# pcb-inductive-sensor2.net
KiCad netlist of a schematic drawn in EAGLE
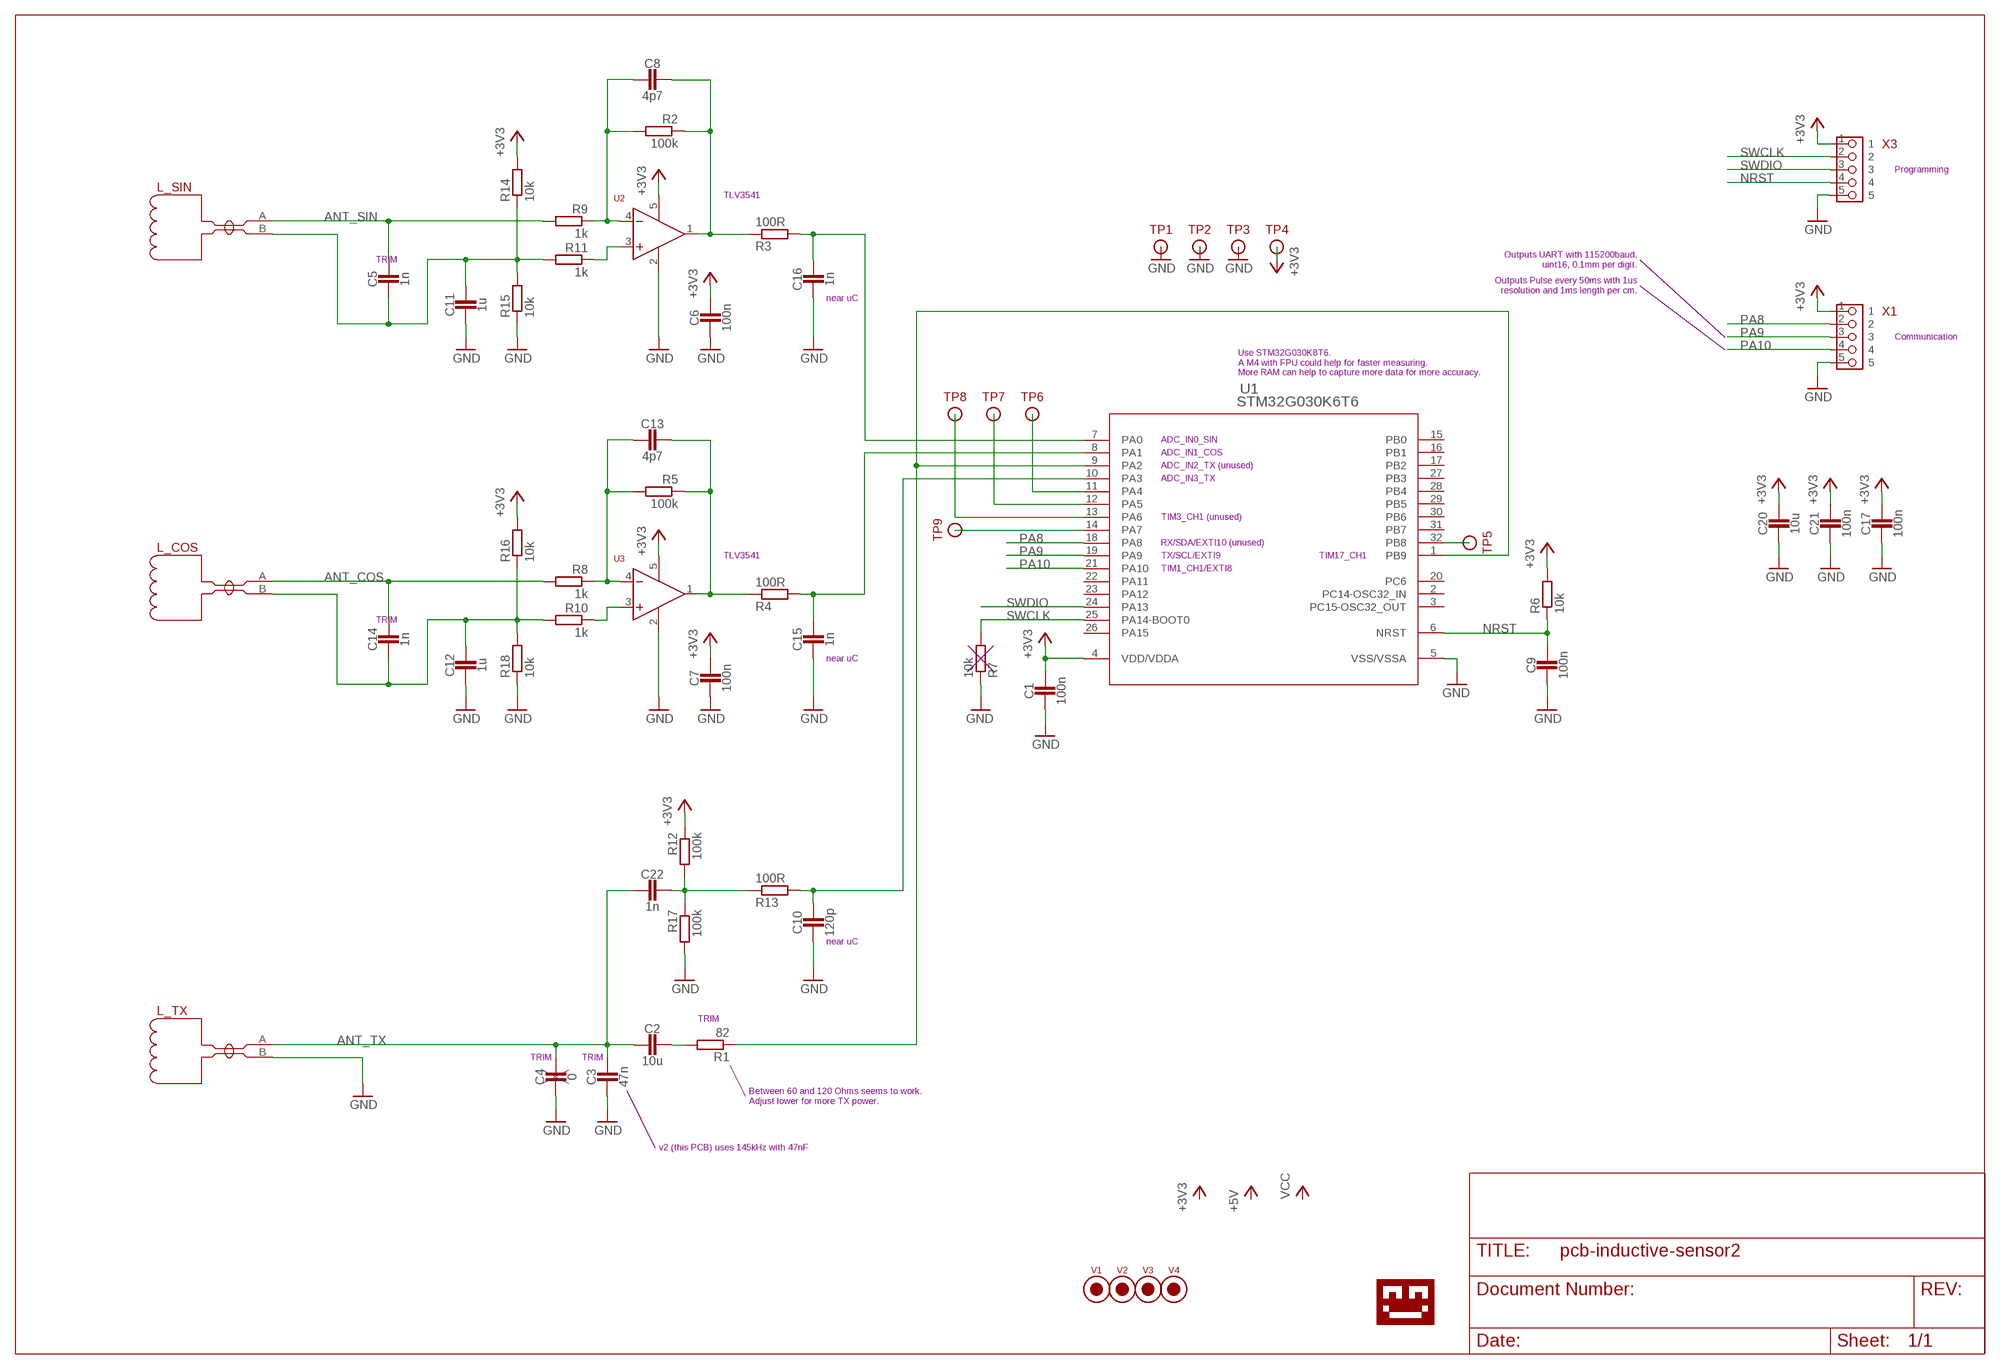
[diagram p0: schematic, sheet 1]

(export (version "E")
  (design (tool "Eeschema 10.0.6"))
  (components
    (comp (ref "C1")
      (value "100n")
      (footprint "eagle-import:0603_CAP")
      (libsource (lib "eagle-import") (part "CAPACITOR0603_CAP"))
    )
    (comp (ref "C2")
      (value "10u")
      (footprint "eagle-import:0805_CAP")
      (libsource (lib "eagle-import") (part "CAPACITOR0805_CAP"))
    )
    (comp (ref "C3")
      (value "47n")
      (footprint "eagle-import:0603_CAP")
      (libsource (lib "eagle-import") (part "CAPACITOR0603_CAP"))
    )
    (comp (ref "C4")
      (value "0")
      (footprint "eagle-import:0603_CAP")
      (libsource (lib "eagle-import") (part "CAPACITOR0603_CAP"))
    )
    (comp (ref "C5")
      (value "1n")
      (footprint "eagle-import:0603_CAP")
      (libsource (lib "eagle-import") (part "CAPACITOR0603_CAP"))
    )
    (comp (ref "C6")
      (value "100n")
      (footprint "eagle-import:0603_CAP")
      (libsource (lib "eagle-import") (part "CAPACITOR0603_CAP"))
    )
    (comp (ref "C7")
      (value "100n")
      (footprint "eagle-import:0603_CAP")
      (libsource (lib "eagle-import") (part "CAPACITOR0603_CAP"))
    )
    (comp (ref "C8")
      (value "4p7")
      (footprint "eagle-import:0603_CAP")
      (libsource (lib "eagle-import") (part "CAPACITOR0603_CAP"))
    )
    (comp (ref "C9")
      (value "100n")
      (footprint "eagle-import:0603_CAP")
      (libsource (lib "eagle-import") (part "CAPACITOR0603_CAP"))
    )
    (comp (ref "C10")
      (value "120p")
      (footprint "eagle-import:0603_CAP")
      (libsource (lib "eagle-import") (part "CAPACITOR0603_CAP"))
    )
    (comp (ref "C11")
      (value "1u")
      (footprint "eagle-import:0603_CAP")
      (libsource (lib "eagle-import") (part "CAPACITOR0603_CAP"))
    )
    (comp (ref "C12")
      (value "1u")
      (footprint "eagle-import:0603_CAP")
      (libsource (lib "eagle-import") (part "CAPACITOR0603_CAP"))
    )
    (comp (ref "C13")
      (value "4p7")
      (footprint "eagle-import:0603_CAP")
      (libsource (lib "eagle-import") (part "CAPACITOR0603_CAP"))
    )
    (comp (ref "C14")
      (value "1n")
      (footprint "eagle-import:0603_CAP")
      (libsource (lib "eagle-import") (part "CAPACITOR0603_CAP"))
    )
    (comp (ref "C15")
      (value "1n")
      (footprint "eagle-import:0603_CAP")
      (libsource (lib "eagle-import") (part "CAPACITOR0603_CAP"))
    )
    (comp (ref "C16")
      (value "1n")
      (footprint "eagle-import:0603_CAP")
      (libsource (lib "eagle-import") (part "CAPACITOR0603_CAP"))
    )
    (comp (ref "C17")
      (value "100n")
      (footprint "eagle-import:0603_CAP")
      (libsource (lib "eagle-import") (part "CAPACITOR0603_CAP"))
    )
    (comp (ref "C20")
      (value "10u")
      (footprint "eagle-import:0805_CAP")
      (libsource (lib "eagle-import") (part "CAPACITOR0805_CAP"))
    )
    (comp (ref "C21")
      (value "100n")
      (footprint "eagle-import:0603_CAP")
      (libsource (lib "eagle-import") (part "CAPACITOR0603_CAP"))
    )
    (comp (ref "C22")
      (value "1n")
      (footprint "eagle-import:0603_CAP")
      (libsource (lib "eagle-import") (part "CAPACITOR0603_CAP"))
    )
    (comp (ref "L_COS")
      (value "INDUCTION_SENSOR")
      (footprint "eagle-import:INDUCTIVE_SENSOR_NET_TIE")
      (libsource (lib "eagle-import") (part "INDUCTION_SENSOR"))
    )
    (comp (ref "L_SIN")
      (value "INDUCTION_SENSOR")
      (footprint "eagle-import:INDUCTIVE_SENSOR_NET_TIE")
      (libsource (lib "eagle-import") (part "INDUCTION_SENSOR"))
    )
    (comp (ref "L_TX")
      (value "INDUCTION_SENSOR")
      (footprint "eagle-import:INDUCTIVE_SENSOR_NET_TIE")
      (libsource (lib "eagle-import") (part "INDUCTION_SENSOR"))
    )
    (comp (ref "R1")
      (value "82")
      (footprint "eagle-import:0805_RES")
      (libsource (lib "eagle-import") (part "RESISTOR0805_RES"))
    )
    (comp (ref "R2")
      (value "100k")
      (footprint "eagle-import:0603-RES")
      (libsource (lib "eagle-import") (part "RESISTOR0603_RES"))
    )
    (comp (ref "R3")
      (value "100R")
      (footprint "eagle-import:0603-RES")
      (libsource (lib "eagle-import") (part "RESISTOR0603_RES"))
    )
    (comp (ref "R4")
      (value "100R")
      (footprint "eagle-import:0603-RES")
      (libsource (lib "eagle-import") (part "RESISTOR0603_RES"))
    )
    (comp (ref "R5")
      (value "100k")
      (footprint "eagle-import:0603-RES")
      (libsource (lib "eagle-import") (part "RESISTOR0603_RES"))
    )
    (comp (ref "R6")
      (value "10k")
      (footprint "eagle-import:0603-RES")
      (libsource (lib "eagle-import") (part "RESISTOR0603_RES"))
    )
    (comp (ref "R7")
      (value "10k")
      (footprint "eagle-import:0603-RES")
      (libsource (lib "eagle-import") (part "RESISTOR0603_RES"))
    )
    (comp (ref "R8")
      (value "1k")
      (footprint "eagle-import:0603-RES")
      (libsource (lib "eagle-import") (part "RESISTOR0603_RES"))
    )
    (comp (ref "R9")
      (value "1k")
      (footprint "eagle-import:0603-RES")
      (libsource (lib "eagle-import") (part "RESISTOR0603_RES"))
    )
    (comp (ref "R10")
      (value "1k")
      (footprint "eagle-import:0603-RES")
      (libsource (lib "eagle-import") (part "RESISTOR0603_RES"))
    )
    (comp (ref "R11")
      (value "1k")
      (footprint "eagle-import:0603-RES")
      (libsource (lib "eagle-import") (part "RESISTOR0603_RES"))
    )
    (comp (ref "R12")
      (value "100k")
      (footprint "eagle-import:0603-RES")
      (libsource (lib "eagle-import") (part "RESISTOR0603_RES"))
    )
    (comp (ref "R13")
      (value "100R")
      (footprint "eagle-import:0603-RES")
      (libsource (lib "eagle-import") (part "RESISTOR0603_RES"))
    )
    (comp (ref "R14")
      (value "10k")
      (footprint "eagle-import:0603-RES")
      (libsource (lib "eagle-import") (part "RESISTOR0603_RES"))
    )
    (comp (ref "R15")
      (value "10k")
      (footprint "eagle-import:0603-RES")
      (libsource (lib "eagle-import") (part "RESISTOR0603_RES"))
    )
    (comp (ref "R16")
      (value "10k")
      (footprint "eagle-import:0603-RES")
      (libsource (lib "eagle-import") (part "RESISTOR0603_RES"))
    )
    (comp (ref "R17")
      (value "100k")
      (footprint "eagle-import:0603-RES")
      (libsource (lib "eagle-import") (part "RESISTOR0603_RES"))
    )
    (comp (ref "R18")
      (value "10k")
      (footprint "eagle-import:0603-RES")
      (libsource (lib "eagle-import") (part "RESISTOR0603_RES"))
    )
    (comp (ref "TP1")
      (value "TESTPIN")
      (footprint "eagle-import:PIN-SMD-1X1-TEST_1M5")
      (libsource (lib "eagle-import") (part "TESTPIN"))
    )
    (comp (ref "TP2")
      (value "TESTPIN")
      (footprint "eagle-import:PIN-SMD-1X1-TEST_1M5")
      (libsource (lib "eagle-import") (part "TESTPIN"))
    )
    (comp (ref "TP3")
      (value "TESTPIN")
      (footprint "eagle-import:PIN-SMD-1X1-TEST_1M5")
      (libsource (lib "eagle-import") (part "TESTPIN"))
    )
    (comp (ref "TP4")
      (value "TESTPIN")
      (footprint "eagle-import:PIN-SMD-1X1-TEST_1M5")
      (libsource (lib "eagle-import") (part "TESTPIN"))
    )
    (comp (ref "TP5")
      (value "TESTPIN")
      (footprint "eagle-import:PIN-SMD-1X1-TEST_1M5")
      (libsource (lib "eagle-import") (part "TESTPIN"))
    )
    (comp (ref "TP6")
      (value "TESTPIN")
      (footprint "eagle-import:PIN-SMD-1X1-TEST_1M5")
      (libsource (lib "eagle-import") (part "TESTPIN"))
    )
    (comp (ref "TP7")
      (value "TESTPIN")
      (footprint "eagle-import:PIN-SMD-1X1-TEST_1M5")
      (libsource (lib "eagle-import") (part "TESTPIN"))
    )
    (comp (ref "TP8")
      (value "TESTPIN")
      (footprint "eagle-import:PIN-SMD-1X1-TEST_1M5")
      (libsource (lib "eagle-import") (part "TESTPIN"))
    )
    (comp (ref "TP9")
      (value "TESTPIN")
      (footprint "eagle-import:PIN-SMD-1X1-TEST_1M5")
      (libsource (lib "eagle-import") (part "TESTPIN"))
    )
    (comp (ref "U$1")
      (value "LOGO-TOBENG-1MM-FINISH")
      (footprint "eagle-import:TOBENG-1MM-FINISH")
      (libsource (lib "eagle-import") (part "LOGO-TOBENG-1MM-FINISH"))
    )
    (comp (ref "U1")
      (value "STM32G030K6T6")
      (footprint "eagle-import:LQFP-32")
      (fields (field (name "COPYRIGHT") "Copyright (C) 2018 Accelerated Designs. All rights reserved"))
      (libsource (lib "eagle-import") (part "STM32G030K6T6"))
    )
    (comp (ref "U2")
      (value "OPAMP-TLV3541IDBVT")
      (footprint "eagle-import:SOT-23-5")
      (libsource (lib "eagle-import") (part "OPAMP-TLV3541IDBVT"))
    )
    (comp (ref "U3")
      (value "OPAMP-TLV3541IDBVT")
      (footprint "eagle-import:SOT-23-5")
      (libsource (lib "eagle-import") (part "OPAMP-TLV3541IDBVT"))
    )
    (comp (ref "V1")
      (value "FIDUCIAL2MM")
      (footprint "eagle-import:FIDUCIAL_2MM")
      (libsource (lib "eagle-import") (part "FIDUCIAL2MM"))
    )
    (comp (ref "V2")
      (value "FIDUCIAL2MM")
      (footprint "eagle-import:FIDUCIAL_2MM")
      (libsource (lib "eagle-import") (part "FIDUCIAL2MM"))
    )
    (comp (ref "V3")
      (value "FIDUCIAL2MM")
      (footprint "eagle-import:FIDUCIAL_2MM")
      (libsource (lib "eagle-import") (part "FIDUCIAL2MM"))
    )
    (comp (ref "V4")
      (value "FIDUCIAL2MM")
      (footprint "eagle-import:FIDUCIAL_2MM")
      (libsource (lib "eagle-import") (part "FIDUCIAL2MM"))
    )
    (comp (ref "X1")
      (value "PIN_5X1HD")
      (footprint "eagle-import:PIN_5X1_HD")
      (libsource (lib "eagle-import") (part "PIN_5X1HD"))
    )
    (comp (ref "X3")
      (value "PIN_5X1HD")
      (footprint "eagle-import:PIN_5X1_HD")
      (libsource (lib "eagle-import") (part "PIN_5X1HD"))
    )
  )
  (nets
    (net (code "1") (name "+3V3") (class "Default")
      (node (ref "C1") (pin "1") (pinfunction "1_1") (pintype "bidirectional"))
      (node (ref "C17") (pin "1") (pinfunction "1_1") (pintype "bidirectional"))
      (node (ref "C20") (pin "P$1") (pinfunction "1_P$1") (pintype "bidirectional"))
      (node (ref "C21") (pin "1") (pinfunction "1_1") (pintype "bidirectional"))
      (node (ref "C6") (pin "1") (pinfunction "1_1") (pintype "bidirectional"))
      (node (ref "C7") (pin "1") (pinfunction "1_1") (pintype "bidirectional"))
      (node (ref "R12") (pin "1") (pinfunction "1_1") (pintype "passive"))
      (node (ref "R14") (pin "2") (pinfunction "2_2") (pintype "passive"))
      (node (ref "R16") (pin "2") (pinfunction "2_2") (pintype "passive"))
      (node (ref "R6") (pin "2") (pinfunction "2_2") (pintype "passive"))
      (node (ref "TP4") (pin "1") (pinfunction "1_1") (pintype "bidirectional"))
      (node (ref "U1") (pin "4") (pinfunction "VDD/VDDA_4") (pintype "power_in"))
      (node (ref "U2") (pin "5") (pinfunction "VCC_5") (pintype "bidirectional"))
      (node (ref "U3") (pin "5") (pinfunction "VCC_5") (pintype "bidirectional"))
      (node (ref "X1") (pin "1") (pinfunction "1_1") (pintype "bidirectional"))
      (node (ref "X3") (pin "1") (pinfunction "1_1") (pintype "bidirectional"))
    )
    (net (code "3") (name "/ANT_COS") (class "Default")
      (node (ref "C14") (pin "1") (pinfunction "1_1") (pintype "bidirectional"))
      (node (ref "L_COS") (pin "A") (pinfunction "A_A") (pintype "bidirectional"))
      (node (ref "R8") (pin "2") (pinfunction "2_2") (pintype "passive"))
    )
    (net (code "4") (name "/ANT_SIN") (class "Default")
      (node (ref "C5") (pin "1") (pinfunction "1_1") (pintype "bidirectional"))
      (node (ref "L_SIN") (pin "A") (pinfunction "A_A") (pintype "bidirectional"))
      (node (ref "R9") (pin "2") (pinfunction "2_2") (pintype "passive"))
    )
    (net (code "5") (name "/ANT_TX") (class "Default")
      (node (ref "C2") (pin "P$2") (pinfunction "2_P$2") (pintype "bidirectional"))
      (node (ref "C22") (pin "2") (pinfunction "2_2") (pintype "bidirectional"))
      (node (ref "C3") (pin "1") (pinfunction "1_1") (pintype "bidirectional"))
      (node (ref "C4") (pin "1") (pinfunction "1_1") (pintype "bidirectional"))
      (node (ref "L_TX") (pin "A") (pinfunction "A_A") (pintype "bidirectional"))
    )
    (net (code "6") (name "/NRST") (class "Default")
      (node (ref "C9") (pin "1") (pinfunction "1_1") (pintype "bidirectional"))
      (node (ref "R6") (pin "1") (pinfunction "1_1") (pintype "passive"))
      (node (ref "U1") (pin "6") (pinfunction "NRST_6") (pintype "bidirectional"))
      (node (ref "X3") (pin "4") (pinfunction "4_4") (pintype "bidirectional"))
    )
    (net (code "7") (name "/PA8") (class "Default")
      (node (ref "U1") (pin "18") (pinfunction "PA8_18") (pintype "bidirectional"))
      (node (ref "X1") (pin "2") (pinfunction "2_2") (pintype "bidirectional"))
    )
    (net (code "8") (name "/PA9") (class "Default")
      (node (ref "U1") (pin "19") (pinfunction "PA9_19") (pintype "bidirectional"))
      (node (ref "X1") (pin "3") (pinfunction "3_3") (pintype "bidirectional"))
    )
    (net (code "9") (name "/PA10") (class "Default")
      (node (ref "U1") (pin "21") (pinfunction "PA10_21") (pintype "bidirectional"))
      (node (ref "X1") (pin "4") (pinfunction "4_4") (pintype "bidirectional"))
    )
    (net (code "10") (name "/SWCLK") (class "Default")
      (node (ref "R7") (pin "2") (pinfunction "2_2") (pintype "passive"))
      (node (ref "U1") (pin "25") (pinfunction "PA14-BOOT0_25") (pintype "bidirectional"))
      (node (ref "X3") (pin "2") (pinfunction "2_2") (pintype "bidirectional"))
    )
    (net (code "11") (name "/SWDIO") (class "Default")
      (node (ref "U1") (pin "24") (pinfunction "PA13_24") (pintype "bidirectional"))
      (node (ref "X3") (pin "3") (pinfunction "3_3") (pintype "bidirectional"))
    )
    (net (code "12") (name "GND") (class "Default")
      (node (ref "C1") (pin "2") (pinfunction "2_2") (pintype "bidirectional"))
      (node (ref "C10") (pin "2") (pinfunction "2_2") (pintype "bidirectional"))
      (node (ref "C11") (pin "2") (pinfunction "2_2") (pintype "bidirectional"))
      (node (ref "C12") (pin "2") (pinfunction "2_2") (pintype "bidirectional"))
      (node (ref "C15") (pin "2") (pinfunction "2_2") (pintype "bidirectional"))
      (node (ref "C16") (pin "2") (pinfunction "2_2") (pintype "bidirectional"))
      (node (ref "C17") (pin "2") (pinfunction "2_2") (pintype "bidirectional"))
      (node (ref "C20") (pin "P$2") (pinfunction "2_P$2") (pintype "bidirectional"))
      (node (ref "C21") (pin "2") (pinfunction "2_2") (pintype "bidirectional"))
      (node (ref "C3") (pin "2") (pinfunction "2_2") (pintype "bidirectional"))
      (node (ref "C4") (pin "2") (pinfunction "2_2") (pintype "bidirectional"))
      (node (ref "C6") (pin "2") (pinfunction "2_2") (pintype "bidirectional"))
      (node (ref "C7") (pin "2") (pinfunction "2_2") (pintype "bidirectional"))
      (node (ref "C9") (pin "2") (pinfunction "2_2") (pintype "bidirectional"))
      (node (ref "L_TX") (pin "B") (pinfunction "B_B") (pintype "bidirectional"))
      (node (ref "R15") (pin "1") (pinfunction "1_1") (pintype "passive"))
      (node (ref "R17") (pin "2") (pinfunction "2_2") (pintype "passive"))
      (node (ref "R18") (pin "1") (pinfunction "1_1") (pintype "passive"))
      (node (ref "R7") (pin "1") (pinfunction "1_1") (pintype "passive"))
      (node (ref "TP1") (pin "1") (pinfunction "1_1") (pintype "bidirectional"))
      (node (ref "TP2") (pin "1") (pinfunction "1_1") (pintype "bidirectional"))
      (node (ref "TP3") (pin "1") (pinfunction "1_1") (pintype "bidirectional"))
      (node (ref "U1") (pin "5") (pinfunction "VSS/VSSA_5") (pintype "power_in"))
      (node (ref "U2") (pin "2") (pinfunction "GND_2") (pintype "bidirectional"))
      (node (ref "U3") (pin "2") (pinfunction "GND_2") (pintype "bidirectional"))
      (node (ref "X1") (pin "5") (pinfunction "5_5") (pintype "bidirectional"))
      (node (ref "X3") (pin "5") (pinfunction "5_5") (pintype "bidirectional"))
    )
    (net (code "13") (name "Net-(C2-1)") (class "Default")
      (node (ref "C2") (pin "P$1") (pinfunction "1_P$1") (pintype "bidirectional"))
      (node (ref "R1") (pin "2") (pinfunction "2_2") (pintype "passive"))
    )
    (net (code "14") (name "Net-(C11-Pad1)") (class "Default")
      (node (ref "C11") (pin "1") (pinfunction "1_1") (pintype "bidirectional"))
      (node (ref "C5") (pin "2") (pinfunction "2_2") (pintype "bidirectional"))
      (node (ref "L_SIN") (pin "B") (pinfunction "B_B") (pintype "bidirectional"))
      (node (ref "R11") (pin "2") (pinfunction "2_2") (pintype "passive"))
      (node (ref "R14") (pin "1") (pinfunction "1_1") (pintype "passive"))
      (node (ref "R15") (pin "2") (pinfunction "2_2") (pintype "passive"))
    )
    (net (code "15") (name "Net-(C12-Pad1)") (class "Default")
      (node (ref "C12") (pin "1") (pinfunction "1_1") (pintype "bidirectional"))
      (node (ref "C14") (pin "2") (pinfunction "2_2") (pintype "bidirectional"))
      (node (ref "L_COS") (pin "B") (pinfunction "B_B") (pintype "bidirectional"))
      (node (ref "R10") (pin "2") (pinfunction "2_2") (pintype "passive"))
      (node (ref "R16") (pin "1") (pinfunction "1_1") (pintype "passive"))
      (node (ref "R18") (pin "2") (pinfunction "2_2") (pintype "passive"))
    )
    (net (code "16") (name "Net-(C22-Pad1)") (class "Default")
      (node (ref "C22") (pin "1") (pinfunction "1_1") (pintype "bidirectional"))
      (node (ref "R12") (pin "2") (pinfunction "2_2") (pintype "passive"))
      (node (ref "R13") (pin "1") (pinfunction "1_1") (pintype "passive"))
      (node (ref "R17") (pin "1") (pinfunction "1_1") (pintype "passive"))
    )
    (net (code "17") (name "Net-(U1-PA0)") (class "Default")
      (node (ref "C16") (pin "1") (pinfunction "1_1") (pintype "bidirectional"))
      (node (ref "R3") (pin "2") (pinfunction "2_2") (pintype "passive"))
      (node (ref "U1") (pin "7") (pinfunction "PA0_7") (pintype "bidirectional"))
    )
    (net (code "18") (name "Net-(U1-PA1)") (class "Default")
      (node (ref "C15") (pin "1") (pinfunction "1_1") (pintype "bidirectional"))
      (node (ref "R4") (pin "2") (pinfunction "2_2") (pintype "passive"))
      (node (ref "U1") (pin "8") (pinfunction "PA1_8") (pintype "bidirectional"))
    )
    (net (code "19") (name "Net-(U1-PA2)") (class "Default")
      (node (ref "R1") (pin "1") (pinfunction "1_1") (pintype "passive"))
      (node (ref "U1") (pin "1") (pinfunction "PB9_1") (pintype "bidirectional"))
      (node (ref "U1") (pin "9") (pinfunction "PA2_9") (pintype "bidirectional"))
    )
    (net (code "20") (name "Net-(U1-PA3)") (class "Default")
      (node (ref "C10") (pin "1") (pinfunction "1_1") (pintype "bidirectional"))
      (node (ref "R13") (pin "2") (pinfunction "2_2") (pintype "passive"))
      (node (ref "U1") (pin "10") (pinfunction "PA3_10") (pintype "bidirectional"))
    )
    (net (code "21") (name "Net-(U1-PA4)") (class "Default")
      (node (ref "TP6") (pin "1") (pinfunction "1_1") (pintype "bidirectional"))
      (node (ref "U1") (pin "11") (pinfunction "PA4_11") (pintype "bidirectional"))
    )
    (net (code "22") (name "Net-(U1-PA5)") (class "Default")
      (node (ref "TP7") (pin "1") (pinfunction "1_1") (pintype "bidirectional"))
      (node (ref "U1") (pin "12") (pinfunction "PA5_12") (pintype "bidirectional"))
    )
    (net (code "23") (name "Net-(U1-PA6)") (class "Default")
      (node (ref "TP8") (pin "1") (pinfunction "1_1") (pintype "bidirectional"))
      (node (ref "U1") (pin "13") (pinfunction "PA6_13") (pintype "bidirectional"))
    )
    (net (code "24") (name "Net-(U1-PA7)") (class "Default")
      (node (ref "TP9") (pin "1") (pinfunction "1_1") (pintype "bidirectional"))
      (node (ref "U1") (pin "14") (pinfunction "PA7_14") (pintype "bidirectional"))
    )
    (net (code "25") (name "Net-(U1-PB8)") (class "Default")
      (node (ref "TP5") (pin "1") (pinfunction "1_1") (pintype "bidirectional"))
      (node (ref "U1") (pin "32") (pinfunction "PB8_32") (pintype "bidirectional"))
    )
    (net (code "26") (name "Net-(U2-+)") (class "Default")
      (node (ref "R11") (pin "1") (pinfunction "1_1") (pintype "passive"))
      (node (ref "U2") (pin "3") (pinfunction "+_3") (pintype "bidirectional"))
    )
    (net (code "27") (name "Net-(U2--)") (class "Default")
      (node (ref "C8") (pin "2") (pinfunction "2_2") (pintype "bidirectional"))
      (node (ref "R2") (pin "2") (pinfunction "2_2") (pintype "passive"))
      (node (ref "R9") (pin "1") (pinfunction "1_1") (pintype "passive"))
      (node (ref "U2") (pin "4") (pinfunction "-_4") (pintype "bidirectional"))
    )
    (net (code "28") (name "Net-(U2-OUT)") (class "Default")
      (node (ref "C8") (pin "1") (pinfunction "1_1") (pintype "bidirectional"))
      (node (ref "R2") (pin "1") (pinfunction "1_1") (pintype "passive"))
      (node (ref "R3") (pin "1") (pinfunction "1_1") (pintype "passive"))
      (node (ref "U2") (pin "1") (pinfunction "OUT_1") (pintype "bidirectional"))
    )
    (net (code "29") (name "Net-(U3-+)") (class "Default")
      (node (ref "R10") (pin "1") (pinfunction "1_1") (pintype "passive"))
      (node (ref "U3") (pin "3") (pinfunction "+_3") (pintype "bidirectional"))
    )
    (net (code "30") (name "Net-(U3--)") (class "Default")
      (node (ref "C13") (pin "2") (pinfunction "2_2") (pintype "bidirectional"))
      (node (ref "R5") (pin "2") (pinfunction "2_2") (pintype "passive"))
      (node (ref "R8") (pin "1") (pinfunction "1_1") (pintype "passive"))
      (node (ref "U3") (pin "4") (pinfunction "-_4") (pintype "bidirectional"))
    )
    (net (code "31") (name "Net-(U3-OUT)") (class "Default")
      (node (ref "C13") (pin "1") (pinfunction "1_1") (pintype "bidirectional"))
      (node (ref "R4") (pin "1") (pinfunction "1_1") (pintype "passive"))
      (node (ref "R5") (pin "1") (pinfunction "1_1") (pintype "passive"))
      (node (ref "U3") (pin "1") (pinfunction "OUT_1") (pintype "bidirectional"))
    )
    (net (code "33") (name "unconnected-(U1-PA11-Pad22)") (class "Default")
      (node (ref "U1") (pin "22") (pinfunction "PA11_22") (pintype "bidirectional"))
    )
    (net (code "34") (name "unconnected-(U1-PA12-Pad23)") (class "Default")
      (node (ref "U1") (pin "23") (pinfunction "PA12_23") (pintype "bidirectional"))
    )
    (net (code "35") (name "unconnected-(U1-PA15-Pad26)") (class "Default")
      (node (ref "U1") (pin "26") (pinfunction "PA15_26") (pintype "bidirectional"))
    )
    (net (code "36") (name "unconnected-(U1-PB0-Pad15)") (class "Default")
      (node (ref "U1") (pin "15") (pinfunction "PB0_15") (pintype "bidirectional"))
    )
    (net (code "37") (name "unconnected-(U1-PB1-Pad16)") (class "Default")
      (node (ref "U1") (pin "16") (pinfunction "PB1_16") (pintype "bidirectional"))
    )
    (net (code "38") (name "unconnected-(U1-PB2-Pad17)") (class "Default")
      (node (ref "U1") (pin "17") (pinfunction "PB2_17") (pintype "bidirectional"))
    )
    (net (code "39") (name "unconnected-(U1-PB3-Pad27)") (class "Default")
      (node (ref "U1") (pin "27") (pinfunction "PB3_27") (pintype "bidirectional"))
    )
    (net (code "40") (name "unconnected-(U1-PB4-Pad28)") (class "Default")
      (node (ref "U1") (pin "28") (pinfunction "PB4_28") (pintype "bidirectional"))
    )
    (net (code "41") (name "unconnected-(U1-PB5-Pad29)") (class "Default")
      (node (ref "U1") (pin "29") (pinfunction "PB5_29") (pintype "bidirectional"))
    )
    (net (code "42") (name "unconnected-(U1-PB6-Pad30)") (class "Default")
      (node (ref "U1") (pin "30") (pinfunction "PB6_30") (pintype "bidirectional"))
    )
    (net (code "43") (name "unconnected-(U1-PB7-Pad31)") (class "Default")
      (node (ref "U1") (pin "31") (pinfunction "PB7_31") (pintype "bidirectional"))
    )
    (net (code "44") (name "unconnected-(U1-PC6-Pad20)") (class "Default")
      (node (ref "U1") (pin "20") (pinfunction "PC6_20") (pintype "bidirectional"))
    )
    (net (code "45") (name "unconnected-(U1-PC14-OSC32_IN-Pad2)") (class "Default")
      (node (ref "U1") (pin "2") (pinfunction "PC14-OSC32_IN_2") (pintype "bidirectional"))
    )
    (net (code "46") (name "unconnected-(U1-PC15-OSC32_OUT-Pad3)") (class "Default")
      (node (ref "U1") (pin "3") (pinfunction "PC15-OSC32_OUT_3") (pintype "bidirectional"))
    )
  )
)
